# KeyPad.net
KiCad netlist of a schematic drawn in Altium Designer
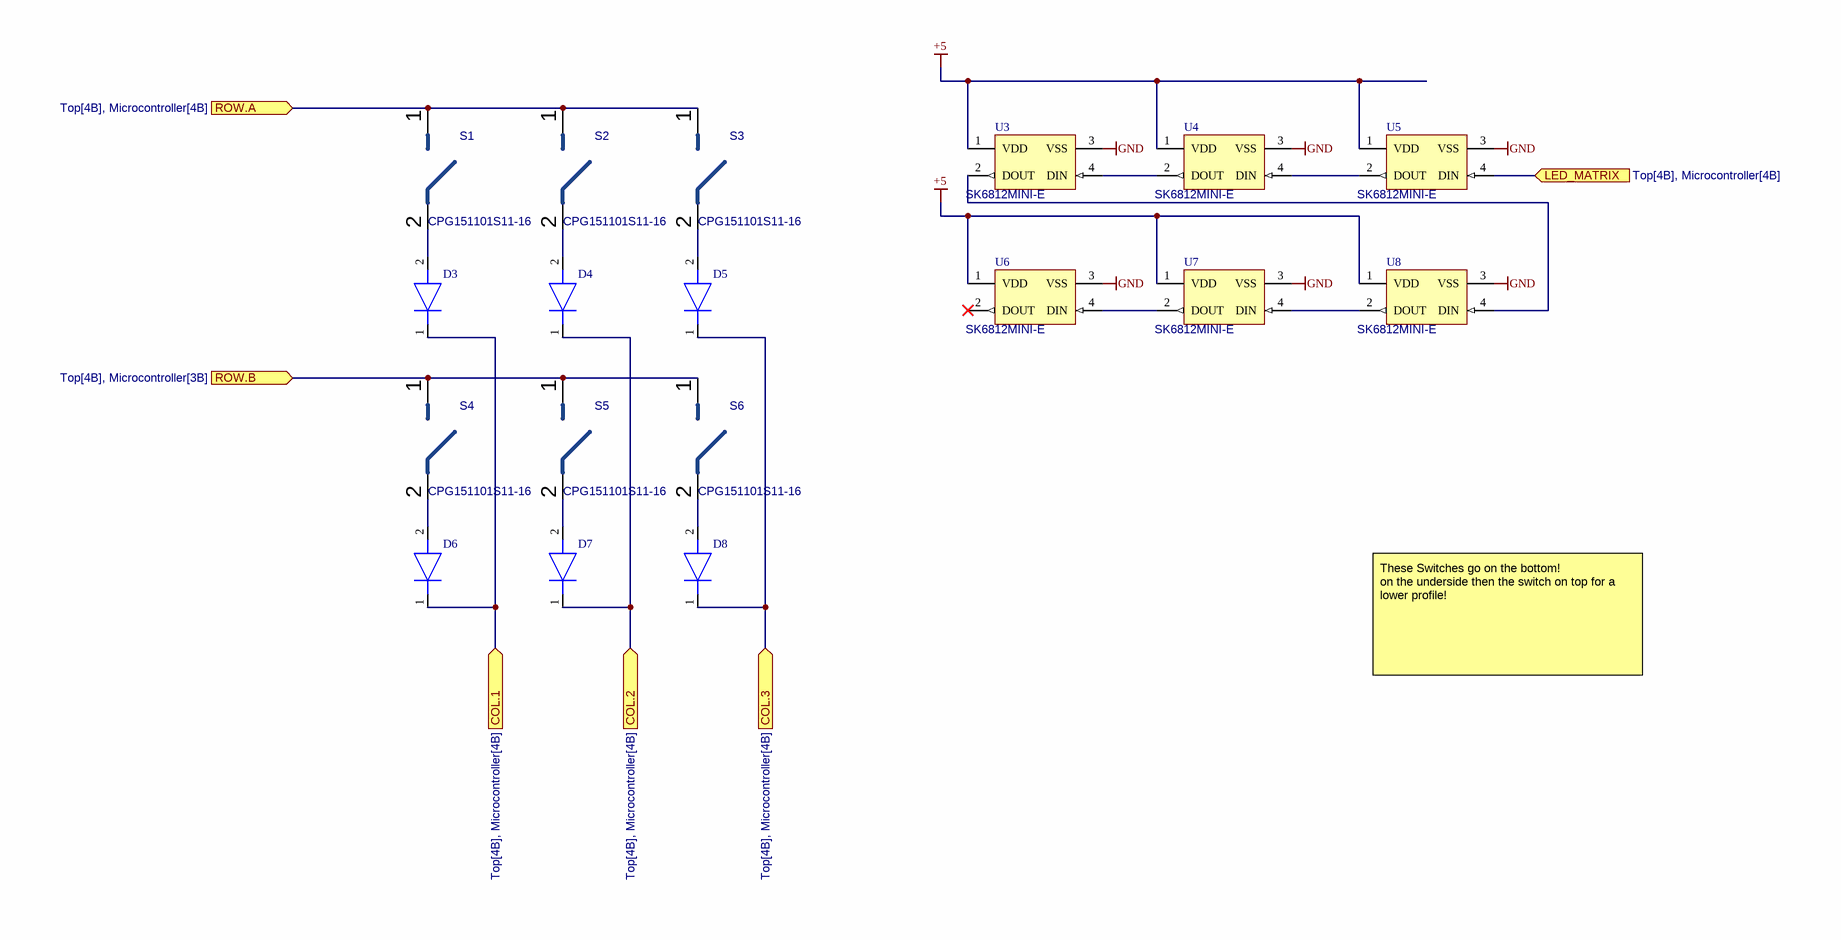
[diagram p0: KeyPad.SchDoc]

(export (version "E")
  (design (tool "Eeschema 10.0.6"))
  (components
    (comp (ref "D3")
      (value "NSVR1020MW2T1G")
      (footprint "SOD2512X110N")
      (description "Diode")
      (fields (field (name "MOUSER PART NUMBER") "863-NSVR1020MW2T1G"))
      (libsource (lib "Curtin Motorsport Team") (part "NSVR1020MW2T1G"))
    )
    (comp (ref "D4")
      (value "NSVR1020MW2T1G")
      (footprint "SOD2512X110N")
      (description "Diode")
      (fields (field (name "MOUSER PART NUMBER") "863-NSVR1020MW2T1G"))
      (libsource (lib "Curtin Motorsport Team") (part "NSVR1020MW2T1G"))
    )
    (comp (ref "D5")
      (value "NSVR1020MW2T1G")
      (footprint "SOD2512X110N")
      (description "Diode")
      (fields (field (name "MOUSER PART NUMBER") "863-NSVR1020MW2T1G"))
      (libsource (lib "Curtin Motorsport Team") (part "NSVR1020MW2T1G"))
    )
    (comp (ref "D6")
      (value "NSVR1020MW2T1G")
      (footprint "SOD2512X110N")
      (description "Diode")
      (fields (field (name "MOUSER PART NUMBER") "863-NSVR1020MW2T1G"))
      (libsource (lib "Curtin Motorsport Team") (part "NSVR1020MW2T1G"))
    )
    (comp (ref "D7")
      (value "NSVR1020MW2T1G")
      (footprint "SOD2512X110N")
      (description "Diode")
      (fields (field (name "MOUSER PART NUMBER") "863-NSVR1020MW2T1G"))
      (libsource (lib "Curtin Motorsport Team") (part "NSVR1020MW2T1G"))
    )
    (comp (ref "D8")
      (value "NSVR1020MW2T1G")
      (footprint "SOD2512X110N")
      (description "Diode")
      (fields (field (name "MOUSER PART NUMBER") "863-NSVR1020MW2T1G"))
      (libsource (lib "Curtin Motorsport Team") (part "NSVR1020MW2T1G"))
    )
    (comp (ref "S1")
      (value "CPG151101S11-16")
      (footprint "CPG151101S11-16-Footprint-1")
      (libsource (lib "Curtin Motorsport Team") (part "CPG151101S11-16-Symbol-1"))
    )
    (comp (ref "S2")
      (value "CPG151101S11-16")
      (footprint "CPG151101S11-16-Footprint-1")
      (libsource (lib "Curtin Motorsport Team") (part "CPG151101S11-16-Symbol-1"))
    )
    (comp (ref "S3")
      (value "CPG151101S11-16")
      (footprint "CPG151101S11-16-Footprint-1")
      (libsource (lib "Curtin Motorsport Team") (part "CPG151101S11-16-Symbol-1"))
    )
    (comp (ref "S4")
      (value "CPG151101S11-16")
      (footprint "CPG151101S11-16-Footprint-1")
      (libsource (lib "Curtin Motorsport Team") (part "CPG151101S11-16-Symbol-1"))
    )
    (comp (ref "S5")
      (value "CPG151101S11-16")
      (footprint "CPG151101S11-16-Footprint-1")
      (libsource (lib "Curtin Motorsport Team") (part "CPG151101S11-16-Symbol-1"))
    )
    (comp (ref "S6")
      (value "CPG151101S11-16")
      (footprint "CPG151101S11-16-Footprint-1")
      (libsource (lib "Curtin Motorsport Team") (part "CPG151101S11-16-Symbol-1"))
    )
    (comp (ref "U3")
      (value "SK6812MINI-E")
      (footprint "Copy of ADAI-WS2812B_V")
      (fields
        (field (name "MANUFACTURER") "Adafruit Industries")
        (field (name "PACKAGE REFERENCE") "SK6812MINI-E")
      )
      (libsource (lib "Curtin Motorsport Team") (part "Addressable RGB"))
    )
    (comp (ref "U4")
      (value "SK6812MINI-E")
      (footprint "Copy of ADAI-WS2812B_V")
      (fields
        (field (name "MANUFACTURER") "Adafruit Industries")
        (field (name "PACKAGE REFERENCE") "SK6812MINI-E")
      )
      (libsource (lib "Curtin Motorsport Team") (part "Addressable RGB"))
    )
    (comp (ref "U5")
      (value "SK6812MINI-E")
      (footprint "Copy of ADAI-WS2812B_V")
      (fields
        (field (name "MANUFACTURER") "Adafruit Industries")
        (field (name "PACKAGE REFERENCE") "SK6812MINI-E")
      )
      (libsource (lib "Curtin Motorsport Team") (part "Addressable RGB"))
    )
    (comp (ref "U6")
      (value "SK6812MINI-E")
      (footprint "Copy of ADAI-WS2812B_V")
      (fields
        (field (name "MANUFACTURER") "Adafruit Industries")
        (field (name "PACKAGE REFERENCE") "SK6812MINI-E")
      )
      (libsource (lib "Curtin Motorsport Team") (part "Addressable RGB"))
    )
    (comp (ref "U7")
      (value "SK6812MINI-E")
      (footprint "Copy of ADAI-WS2812B_V")
      (fields
        (field (name "MANUFACTURER") "Adafruit Industries")
        (field (name "PACKAGE REFERENCE") "SK6812MINI-E")
      )
      (libsource (lib "Curtin Motorsport Team") (part "Addressable RGB"))
    )
    (comp (ref "U8")
      (value "SK6812MINI-E")
      (footprint "Copy of ADAI-WS2812B_V")
      (fields
        (field (name "MANUFACTURER") "Adafruit Industries")
        (field (name "PACKAGE REFERENCE") "SK6812MINI-E")
      )
      (libsource (lib "Curtin Motorsport Team") (part "Addressable RGB"))
    )
  )
  (nets
    (net (code "1") (name "+5") (class "Default")
      (node (ref "U3") (pin "1") (pinfunction "VDD_1") (pintype "power_in"))
      (node (ref "U4") (pin "1") (pinfunction "VDD_1") (pintype "power_in"))
      (node (ref "U5") (pin "1") (pinfunction "VDD_1") (pintype "power_in"))
      (node (ref "U6") (pin "1") (pinfunction "VDD_1") (pintype "power_in"))
      (node (ref "U7") (pin "1") (pinfunction "VDD_1") (pintype "power_in"))
      (node (ref "U8") (pin "1") (pinfunction "VDD_1") (pintype "power_in"))
    )
    (net (code "2") (name "/COL.1") (class "Default")
      (node (ref "D3") (pin "1") (pinfunction "K_1") (pintype "passive"))
      (node (ref "D6") (pin "1") (pinfunction "K_1") (pintype "passive"))
    )
    (net (code "3") (name "/COL.2") (class "Default")
      (node (ref "D4") (pin "1") (pinfunction "K_1") (pintype "passive"))
      (node (ref "D7") (pin "1") (pinfunction "K_1") (pintype "passive"))
    )
    (net (code "4") (name "/COL.3") (class "Default")
      (node (ref "D5") (pin "1") (pinfunction "K_1") (pintype "passive"))
      (node (ref "D8") (pin "1") (pinfunction "K_1") (pintype "passive"))
    )
    (net (code "5") (name "/LED_MATRIX") (class "Default")
      (node (ref "U5") (pin "4") (pinfunction "DIN_4") (pintype "input"))
    )
    (net (code "6") (name "/ROW.A") (class "Default")
      (node (ref "S1") (pin "1") (pinfunction "1_1") (pintype "passive"))
      (node (ref "S2") (pin "1") (pinfunction "1_1") (pintype "passive"))
      (node (ref "S3") (pin "1") (pinfunction "1_1") (pintype "passive"))
    )
    (net (code "7") (name "/ROW.B") (class "Default")
      (node (ref "S4") (pin "1") (pinfunction "1_1") (pintype "passive"))
      (node (ref "S5") (pin "1") (pinfunction "1_1") (pintype "passive"))
      (node (ref "S6") (pin "1") (pinfunction "1_1") (pintype "passive"))
    )
    (net (code "8") (name "GND") (class "Default")
      (node (ref "U3") (pin "3") (pinfunction "VSS_3") (pintype "power_in"))
      (node (ref "U4") (pin "3") (pinfunction "VSS_3") (pintype "power_in"))
      (node (ref "U5") (pin "3") (pinfunction "VSS_3") (pintype "power_in"))
      (node (ref "U6") (pin "3") (pinfunction "VSS_3") (pintype "power_in"))
      (node (ref "U7") (pin "3") (pinfunction "VSS_3") (pintype "power_in"))
      (node (ref "U8") (pin "3") (pinfunction "VSS_3") (pintype "power_in"))
    )
    (net (code "9") (name "Net-(D3-A)") (class "Default")
      (node (ref "D3") (pin "2") (pinfunction "A_2") (pintype "passive"))
      (node (ref "S1") (pin "2") (pinfunction "2_2") (pintype "passive"))
    )
    (net (code "10") (name "Net-(D4-A)") (class "Default")
      (node (ref "D4") (pin "2") (pinfunction "A_2") (pintype "passive"))
      (node (ref "S2") (pin "2") (pinfunction "2_2") (pintype "passive"))
    )
    (net (code "11") (name "Net-(D5-A)") (class "Default")
      (node (ref "D5") (pin "2") (pinfunction "A_2") (pintype "passive"))
      (node (ref "S3") (pin "2") (pinfunction "2_2") (pintype "passive"))
    )
    (net (code "12") (name "Net-(D6-A)") (class "Default")
      (node (ref "D6") (pin "2") (pinfunction "A_2") (pintype "passive"))
      (node (ref "S4") (pin "2") (pinfunction "2_2") (pintype "passive"))
    )
    (net (code "13") (name "Net-(D7-A)") (class "Default")
      (node (ref "D7") (pin "2") (pinfunction "A_2") (pintype "passive"))
      (node (ref "S5") (pin "2") (pinfunction "2_2") (pintype "passive"))
    )
    (net (code "14") (name "Net-(D8-A)") (class "Default")
      (node (ref "D8") (pin "2") (pinfunction "A_2") (pintype "passive"))
      (node (ref "S6") (pin "2") (pinfunction "2_2") (pintype "passive"))
    )
    (net (code "15") (name "Net-(U3-DIN)") (class "Default")
      (node (ref "U3") (pin "4") (pinfunction "DIN_4") (pintype "input"))
      (node (ref "U4") (pin "2") (pinfunction "DOUT_2") (pintype "output"))
    )
    (net (code "16") (name "Net-(U3-DOUT)") (class "Default")
      (node (ref "U3") (pin "2") (pinfunction "DOUT_2") (pintype "output"))
      (node (ref "U8") (pin "4") (pinfunction "DIN_4") (pintype "input"))
    )
    (net (code "17") (name "Net-(U4-DIN)") (class "Default")
      (node (ref "U4") (pin "4") (pinfunction "DIN_4") (pintype "input"))
      (node (ref "U5") (pin "2") (pinfunction "DOUT_2") (pintype "output"))
    )
    (net (code "18") (name "Net-(U6-DIN)") (class "Default")
      (node (ref "U6") (pin "4") (pinfunction "DIN_4") (pintype "input"))
      (node (ref "U7") (pin "2") (pinfunction "DOUT_2") (pintype "output"))
    )
    (net (code "19") (name "Net-(U7-DIN)") (class "Default")
      (node (ref "U7") (pin "4") (pinfunction "DIN_4") (pintype "input"))
      (node (ref "U8") (pin "2") (pinfunction "DOUT_2") (pintype "output"))
    )
    (net (code "20") (name "unconnected-(U6-DOUT-Pad2)") (class "Default")
      (node (ref "U6") (pin "2") (pinfunction "DOUT_2") (pintype "output+no_connect"))
    )
  )
)
